# P03-UARTs_KEY.net
KiCad netlist of a schematic drawn in Altium Designer
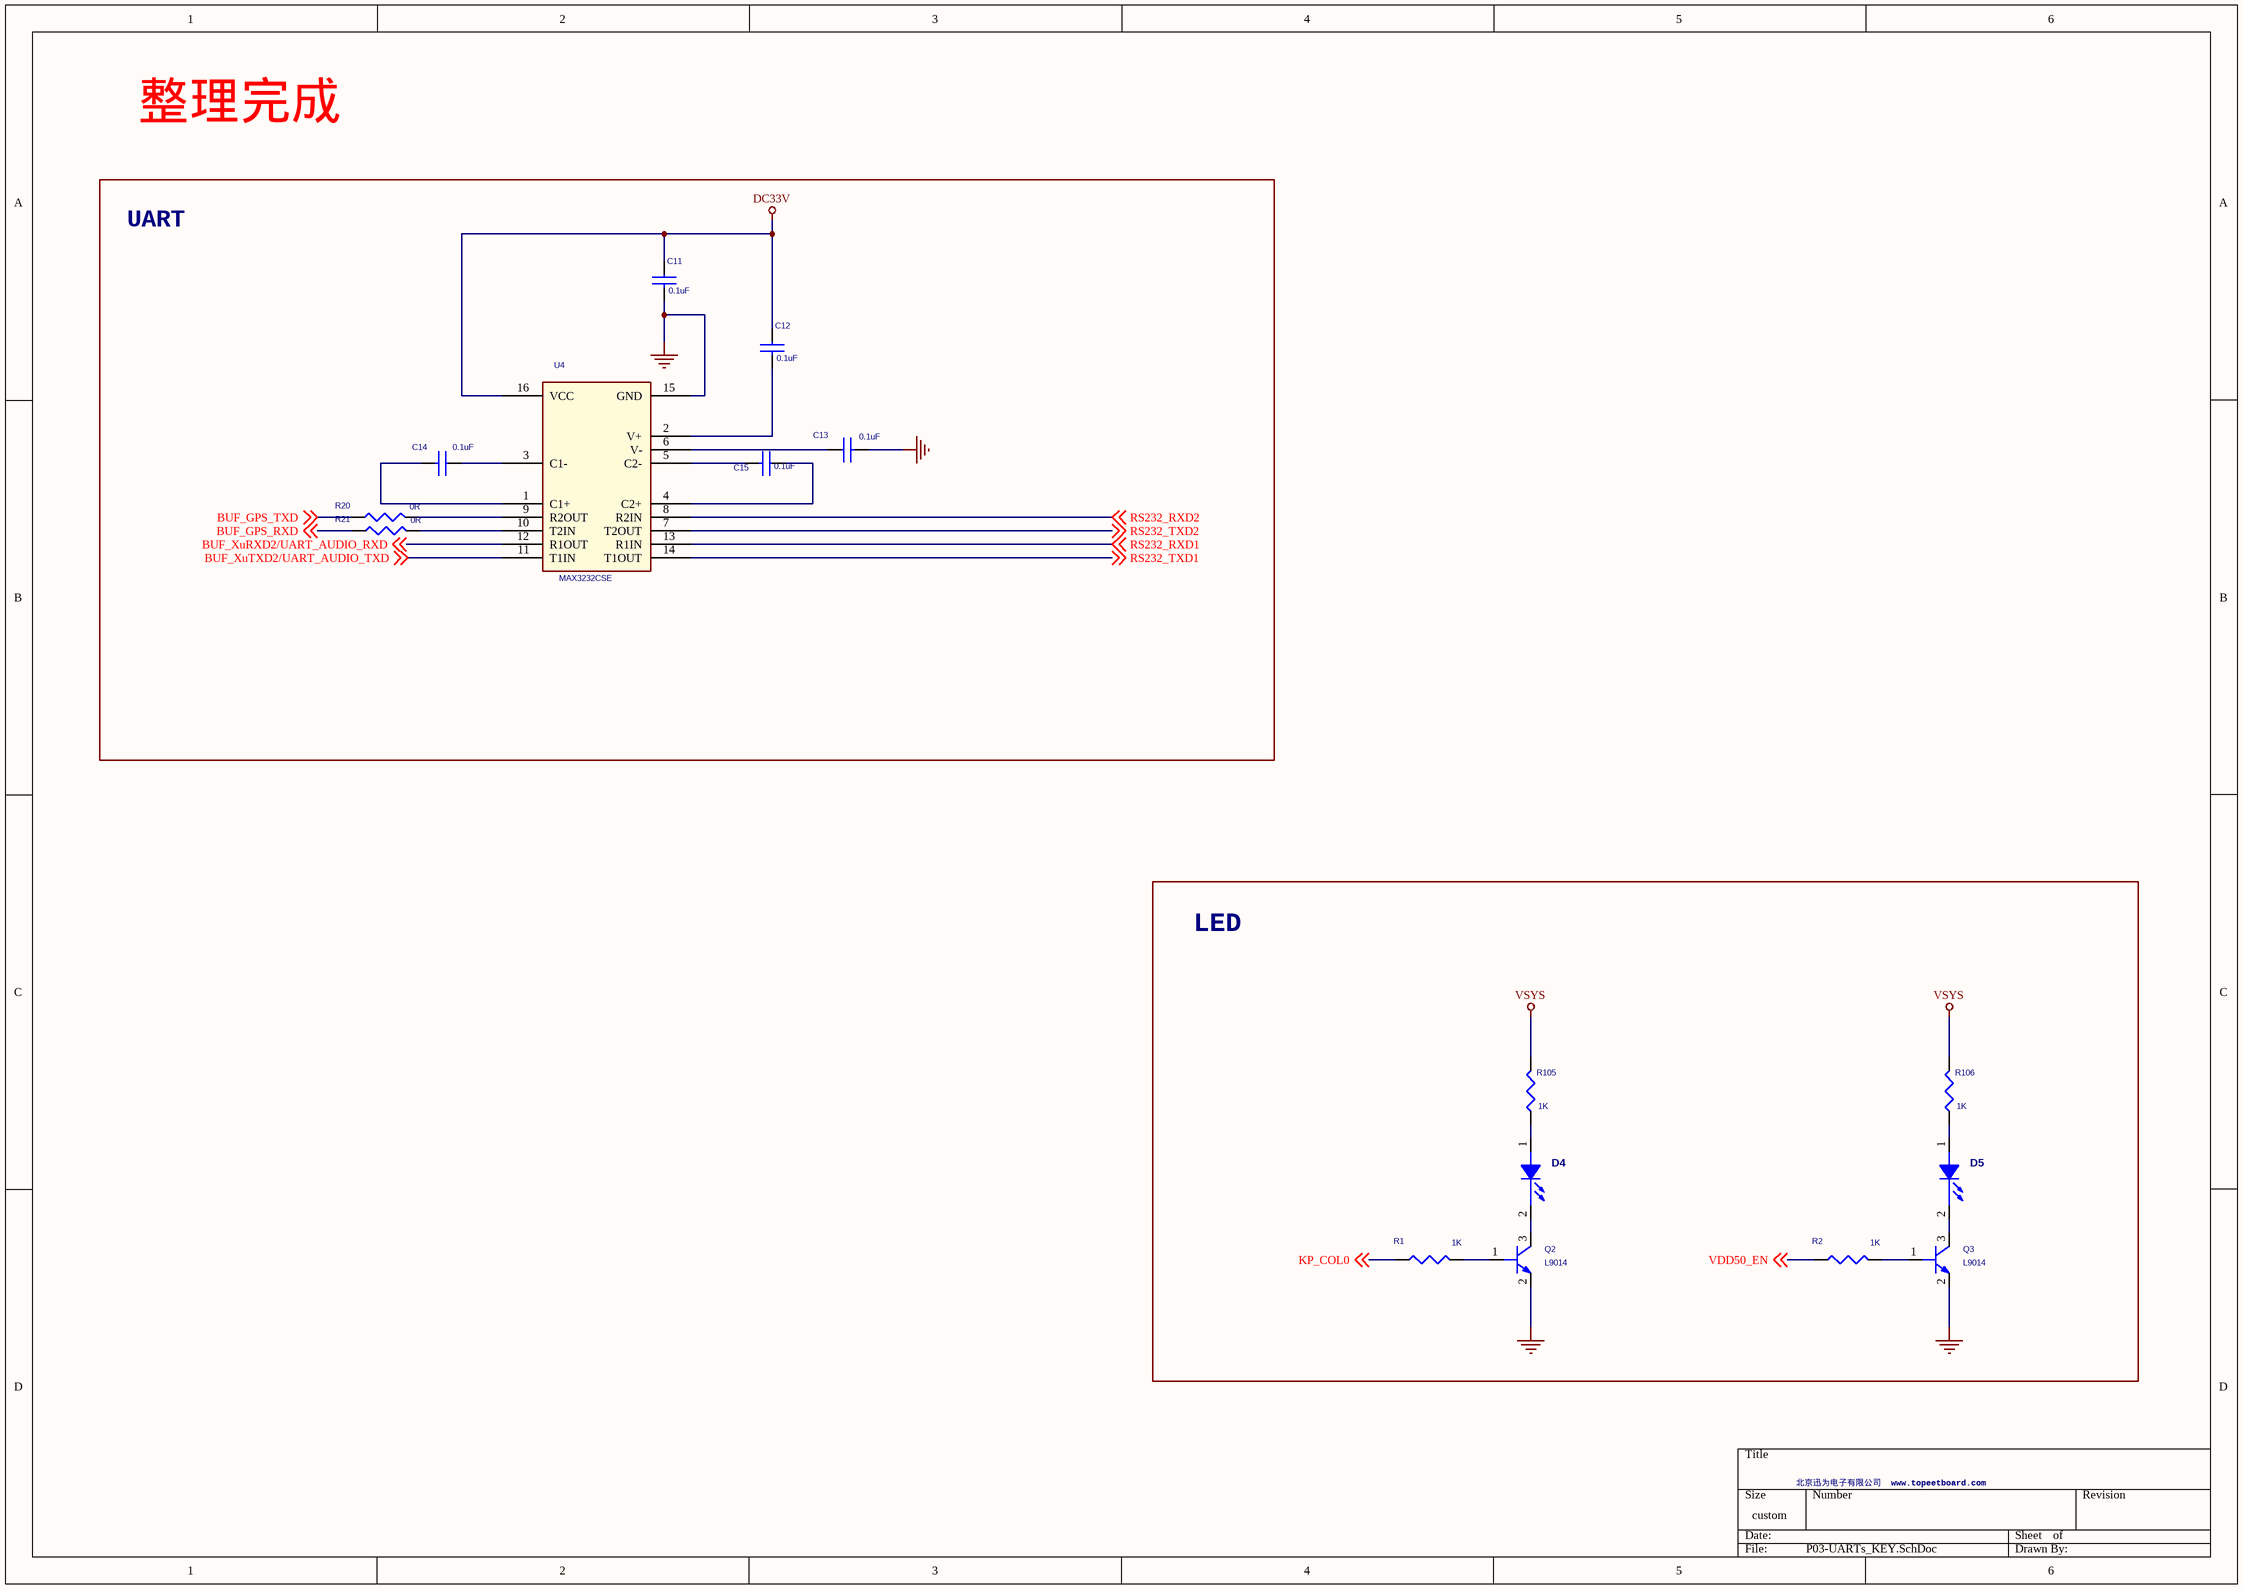
[diagram p0: P03-UARTs_KEY.SchDoc]

(export (version "E")
  (design (tool "Eeschema 10.0.6"))
  (components
    (comp (ref "C11") (value "0.1uF") (footprint "C0603-S") (libsource (lib "*") (part "C0603_0")))
    (comp (ref "C12") (value "0.1uF") (footprint "C0603-S") (libsource (lib "*") (part "C0603_0")))
    (comp (ref "C13") (value "0.1uF") (footprint "C0603-S") (libsource (lib "*") (part "C0603_0")))
    (comp (ref "C14") (value "0.1uF") (footprint "C0603-S") (libsource (lib "*") (part "C0603_0")))
    (comp (ref "C15") (value "0.1uF") (footprint "C0603-S") (libsource (lib "*") (part "C0603_0")))
    (comp (ref "D4")
      (value "LED-Red (SMD 2012)")
      (footprint "LED0603")
      (libsource (lib "*") (part "LED-RED_SMD_1"))
    )
    (comp (ref "D5")
      (value "LED-Red (SMD 2012)")
      (footprint "LED0603")
      (libsource (lib "*") (part "LED-RED_SMD_1"))
    )
    (comp (ref "Q2") (value "L9014") (libsource (lib "*") (part "L14P2/TO_1")))
    (comp (ref "Q3") (value "L9014") (libsource (lib "*") (part "L14P2/TO_1")))
    (comp (ref "R1") (value "1K") (footprint "R0603-S") (libsource (lib "*") (part "R1005_0_Dup1")))
    (comp (ref "R2") (value "1K") (footprint "R0603-S") (libsource (lib "*") (part "R1005_0_Dup1")))
    (comp (ref "R20") (value "0R") (footprint "R0603-S") (libsource (lib "*") (part "R1005_0")))
    (comp (ref "R21") (value "0R") (footprint "R0603-S") (libsource (lib "*") (part "R1005_0")))
    (comp (ref "R105") (value "1K") (footprint "R0603-S") (libsource (lib "*") (part "R1005_0_Dup1")))
    (comp (ref "R106") (value "1K") (footprint "R0603-S") (libsource (lib "*") (part "R1005_0_Dup1")))
    (comp (ref "U4") (value "MAX3232CSE") (footprint "SO-16") (libsource (lib "*") (part "MAX3232EEAE")))
  )
  (nets
    (net (code "1") (name "BUF_GPS_RXD") (class "Default")
      (node (ref "R21") (pin "1") (pinfunction "1_1") (pintype "passive"))
    )
    (net (code "2") (name "BUF_GPS_TXD") (class "Default")
      (node (ref "R20") (pin "1") (pinfunction "1_1") (pintype "passive"))
    )
    (net (code "3") (name "BUF_XuRXD2{slash}UART_AUDIO_RXD") (class "Default")
      (node (ref "U4") (pin "12") (pinfunction "R1OUT_12") (pintype "passive"))
    )
    (net (code "4") (name "BUF_XuTXD2{slash}UART_AUDIO_TXD") (class "Default")
      (node (ref "U4") (pin "11") (pinfunction "T1IN_11") (pintype "passive"))
    )
    (net (code "5") (name "DC33V") (class "Default")
      (node (ref "C11") (pin "1") (pinfunction "1_1") (pintype "passive"))
      (node (ref "C12") (pin "1") (pinfunction "1_1") (pintype "passive"))
      (node (ref "U4") (pin "16") (pinfunction "VCC_16") (pintype "power_in"))
    )
    (net (code "6") (name "GND") (class "Default")
      (node (ref "C11") (pin "2") (pinfunction "2_2") (pintype "passive"))
      (node (ref "C13") (pin "2") (pinfunction "2_2") (pintype "passive"))
      (node (ref "Q2") (pin "2") (pinfunction "EMITTER_2") (pintype "passive"))
      (node (ref "Q3") (pin "2") (pinfunction "EMITTER_2") (pintype "passive"))
      (node (ref "U4") (pin "15") (pinfunction "GND_15") (pintype "power_in"))
    )
    (net (code "7") (name "KP_COL0") (class "Default")
      (node (ref "R1") (pin "2") (pinfunction "2_2") (pintype "passive"))
    )
    (net (code "8") (name "Net-(D4-ANODE)") (class "Default")
      (node (ref "D4") (pin "1") (pinfunction "ANODE_1") (pintype "passive"))
      (node (ref "R105") (pin "1") (pinfunction "1_1") (pintype "passive"))
    )
    (net (code "9") (name "Net-(D4-CATHODE)") (class "Default")
      (node (ref "D4") (pin "2") (pinfunction "CATHODE_2") (pintype "passive"))
      (node (ref "Q2") (pin "3") (pinfunction "COLLECTOR_3") (pintype "passive"))
    )
    (net (code "10") (name "Net-(D5-ANODE)") (class "Default")
      (node (ref "D5") (pin "1") (pinfunction "ANODE_1") (pintype "passive"))
      (node (ref "R106") (pin "1") (pinfunction "1_1") (pintype "passive"))
    )
    (net (code "11") (name "Net-(D5-CATHODE)") (class "Default")
      (node (ref "D5") (pin "2") (pinfunction "CATHODE_2") (pintype "passive"))
      (node (ref "Q3") (pin "3") (pinfunction "COLLECTOR_3") (pintype "passive"))
    )
    (net (code "12") (name "Net-(Q2-BASE)") (class "Default")
      (node (ref "Q2") (pin "1") (pinfunction "BASE_1") (pintype "passive"))
      (node (ref "R1") (pin "1") (pinfunction "1_1") (pintype "passive"))
    )
    (net (code "13") (name "Net-(Q3-BASE)") (class "Default")
      (node (ref "Q3") (pin "1") (pinfunction "BASE_1") (pintype "passive"))
      (node (ref "R2") (pin "1") (pinfunction "1_1") (pintype "passive"))
    )
    (net (code "14") (name "Net-(U4-C1+)") (class "Default")
      (node (ref "C14") (pin "2") (pinfunction "2_2") (pintype "passive"))
      (node (ref "U4") (pin "1") (pinfunction "C1+_1") (pintype "passive"))
    )
    (net (code "15") (name "Net-(U4-C1-)") (class "Default")
      (node (ref "C14") (pin "1") (pinfunction "1_1") (pintype "passive"))
      (node (ref "U4") (pin "3") (pinfunction "C1-_3") (pintype "passive"))
    )
    (net (code "16") (name "Net-(U4-C2+)") (class "Default")
      (node (ref "C15") (pin "1") (pinfunction "1_1") (pintype "passive"))
      (node (ref "U4") (pin "4") (pinfunction "C2+_4") (pintype "passive"))
    )
    (net (code "17") (name "Net-(U4-C2-)") (class "Default")
      (node (ref "C15") (pin "2") (pinfunction "2_2") (pintype "passive"))
      (node (ref "U4") (pin "5") (pinfunction "C2-_5") (pintype "passive"))
    )
    (net (code "18") (name "Net-(U4-R2OUT)") (class "Default")
      (node (ref "R20") (pin "2") (pinfunction "2_2") (pintype "passive"))
      (node (ref "U4") (pin "9") (pinfunction "R2OUT_9") (pintype "passive"))
    )
    (net (code "19") (name "Net-(U4-T2IN)") (class "Default")
      (node (ref "R21") (pin "2") (pinfunction "2_2") (pintype "passive"))
      (node (ref "U4") (pin "10") (pinfunction "T2IN_10") (pintype "passive"))
    )
    (net (code "20") (name "Net-(U4-V+)") (class "Default")
      (node (ref "C12") (pin "2") (pinfunction "2_2") (pintype "passive"))
      (node (ref "U4") (pin "2") (pinfunction "V+_2") (pintype "passive"))
    )
    (net (code "21") (name "Net-(U4-V-)") (class "Default")
      (node (ref "C13") (pin "1") (pinfunction "1_1") (pintype "passive"))
      (node (ref "U4") (pin "6") (pinfunction "V-_6") (pintype "passive"))
    )
    (net (code "22") (name "RS232_RXD1") (class "Default")
      (node (ref "U4") (pin "13") (pinfunction "R1IN_13") (pintype "passive"))
    )
    (net (code "23") (name "RS232_RXD2") (class "Default")
      (node (ref "U4") (pin "8") (pinfunction "R2IN_8") (pintype "passive"))
    )
    (net (code "24") (name "RS232_TXD1") (class "Default")
      (node (ref "U4") (pin "14") (pinfunction "T1OUT_14") (pintype "passive"))
    )
    (net (code "25") (name "RS232_TXD2") (class "Default")
      (node (ref "U4") (pin "7") (pinfunction "T2OUT_7") (pintype "passive"))
    )
    (net (code "26") (name "VDD50_EN") (class "Default")
      (node (ref "R2") (pin "2") (pinfunction "2_2") (pintype "passive"))
    )
    (net (code "27") (name "VSYS") (class "Default")
      (node (ref "R105") (pin "2") (pinfunction "2_2") (pintype "passive"))
      (node (ref "R106") (pin "2") (pinfunction "2_2") (pintype "passive"))
    )
  )
)
